# BatteryProtection.net
KiCad netlist of a schematic drawn in EAGLE
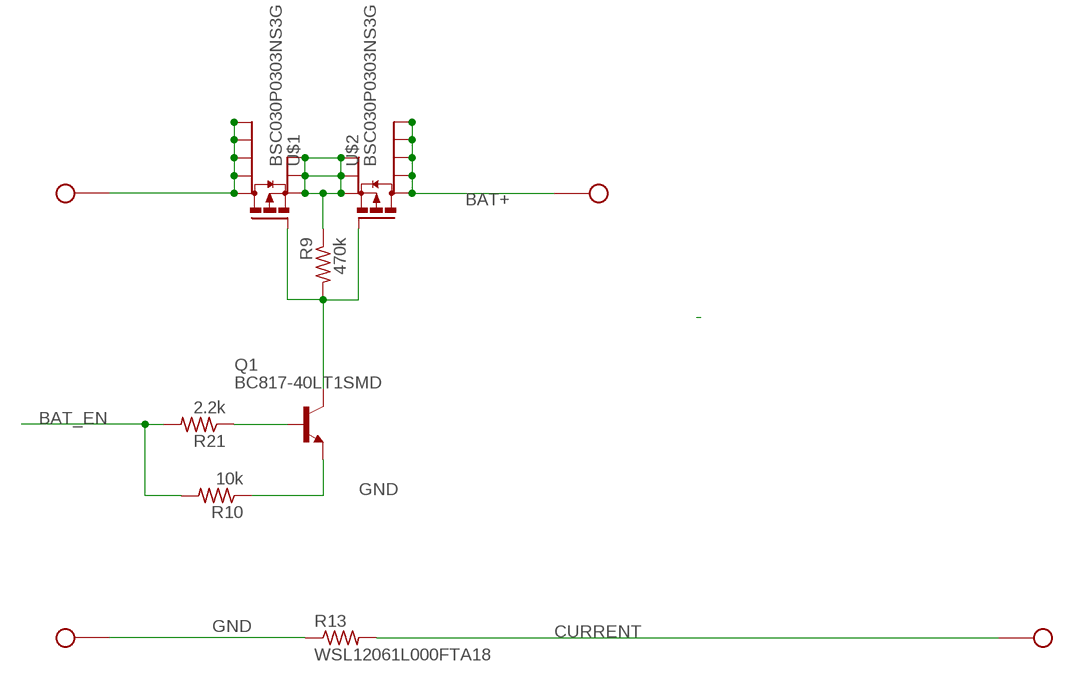
[diagram p0: schematic, sheet 1]
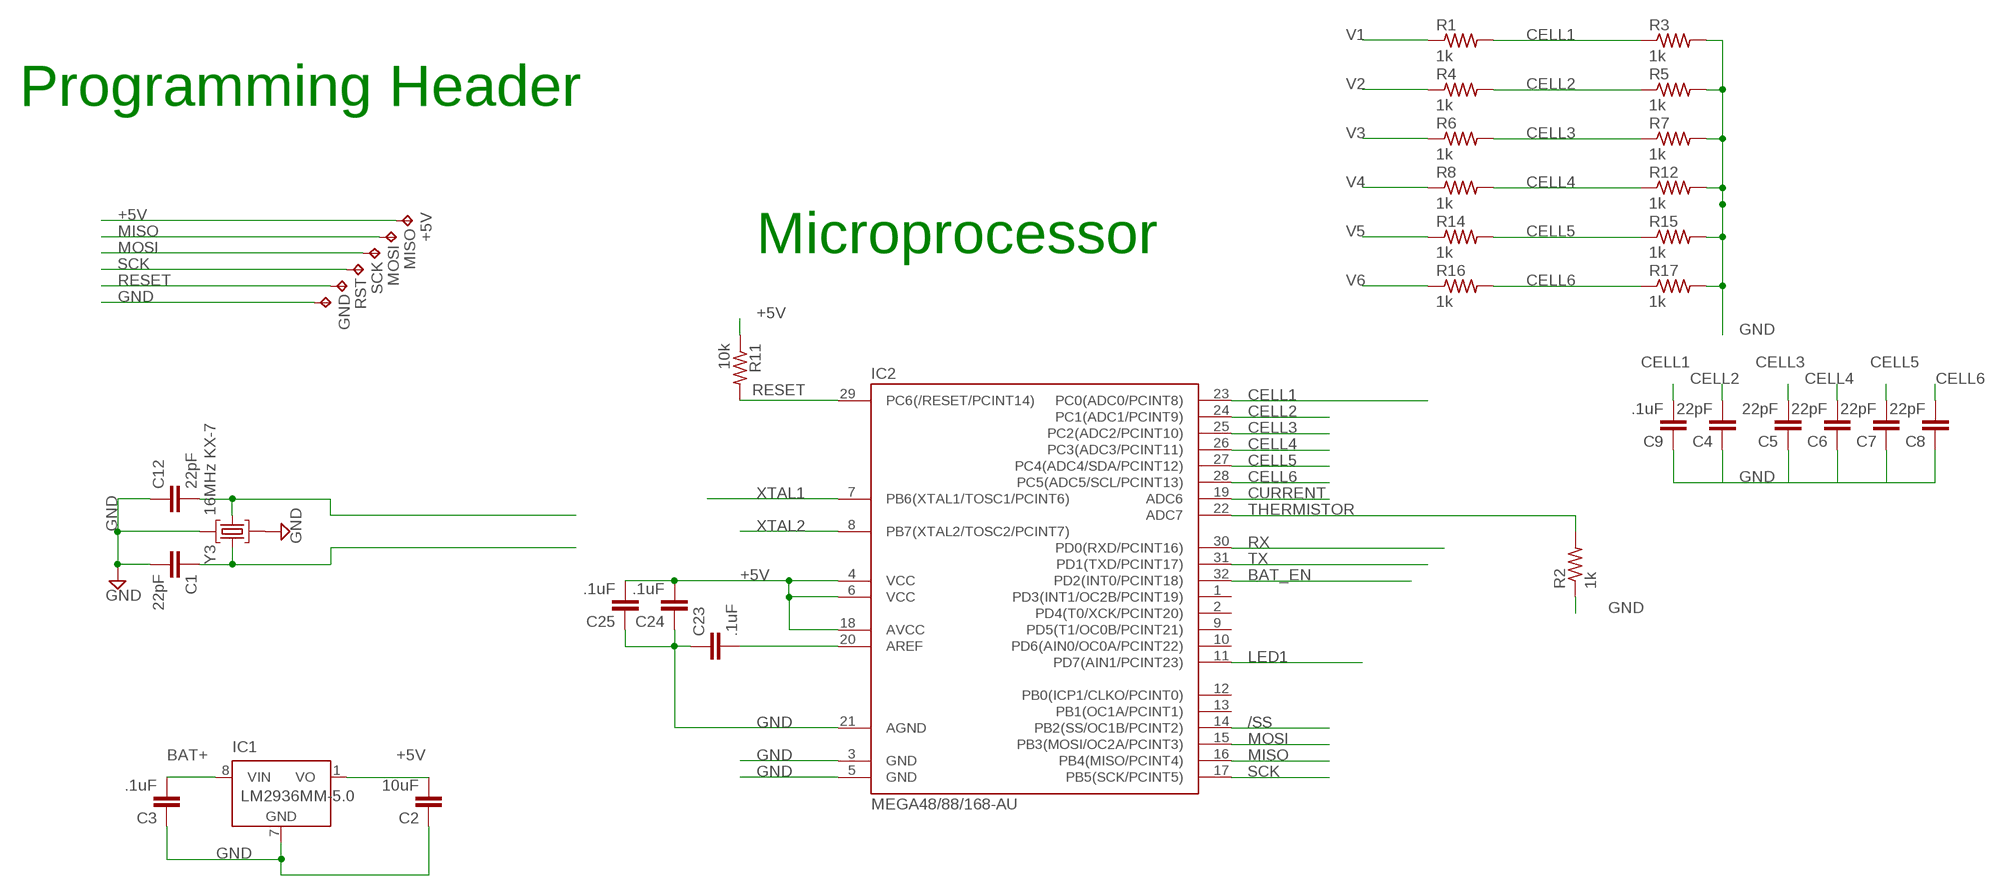
[diagram p1: schematic, sheet 2]

(export (version "E")
  (design (tool "Eeschema 10.0.6"))
  (components
    (comp (ref "+5V")
      (value "TPTP08R")
      (footprint "eagle-import:TP08R")
      (libsource (lib "eagle-import") (part "TPTP08R"))
    )
    (comp (ref "C1")
      (value "22pF")
      (footprint "eagle-import:C0402")
      (libsource (lib "eagle-import") (part "rcl_C-EUC0402"))
    )
    (comp (ref "C2")
      (value "10uF")
      (footprint "eagle-import:C0805")
      (libsource (lib "eagle-import") (part "rcl_C-EUC0805"))
    )
    (comp (ref "C3")
      (value ".1uF")
      (footprint "eagle-import:C0402")
      (libsource (lib "eagle-import") (part "rcl_C-EUC0402"))
    )
    (comp (ref "C4")
      (value "22pF")
      (footprint "eagle-import:C0402")
      (libsource (lib "eagle-import") (part "C-EUC0402"))
    )
    (comp (ref "C5")
      (value "22pF")
      (footprint "eagle-import:C0402")
      (libsource (lib "eagle-import") (part "C-EUC0402"))
    )
    (comp (ref "C6")
      (value "22pF")
      (footprint "eagle-import:C0402")
      (libsource (lib "eagle-import") (part "C-EUC0402"))
    )
    (comp (ref "C7")
      (value "22pF")
      (footprint "eagle-import:C0402")
      (libsource (lib "eagle-import") (part "C-EUC0402"))
    )
    (comp (ref "C8")
      (value "22pF")
      (footprint "eagle-import:C0402")
      (libsource (lib "eagle-import") (part "C-EUC0402"))
    )
    (comp (ref "C9")
      (value ".1uF")
      (footprint "eagle-import:C0402")
      (libsource (lib "eagle-import") (part "rcl_C-EUC0402"))
    )
    (comp (ref "C12")
      (value "22pF")
      (footprint "eagle-import:C0402")
      (libsource (lib "eagle-import") (part "C-EUC0402"))
    )
    (comp (ref "C23")
      (value ".1uF")
      (footprint "eagle-import:C0402")
      (libsource (lib "eagle-import") (part "rcl_C-EUC0402"))
    )
    (comp (ref "C24")
      (value ".1uF")
      (footprint "eagle-import:C0402")
      (libsource (lib "eagle-import") (part "rcl_C-EUC0402"))
    )
    (comp (ref "C25")
      (value ".1uF")
      (footprint "eagle-import:C0402")
      (libsource (lib "eagle-import") (part "rcl_C-EUC0402"))
    )
    (comp (ref "GND")
      (value "TPTP08R")
      (footprint "eagle-import:TP08R")
      (libsource (lib "eagle-import") (part "TPTP08R"))
    )
    (comp (ref "IC1")
      (value "LM2936MM-5.0")
      (footprint "eagle-import:MINI-SO8")
      (fields (field (name "MF") "NATIONAL SEMICONDUCTOR") (field (name "MPN") "LM2936MM-5.0/NOPB"))
      (libsource (lib "eagle-import") (part "LM2936?MM-5.0"))
    )
    (comp (ref "IC2")
      (value "MEGA48/88/168-AU")
      (footprint "eagle-import:TQFP32-08")
      (libsource (lib "eagle-import") (part "MEGA48/88/168-AU"))
    )
    (comp (ref "MISO")
      (value "TPTP08R")
      (footprint "eagle-import:TP08R")
      (libsource (lib "eagle-import") (part "TPTP08R"))
    )
    (comp (ref "MOSI")
      (value "TPTP08R")
      (footprint "eagle-import:TP08R")
      (libsource (lib "eagle-import") (part "TPTP08R"))
    )
    (comp (ref "R1")
      (value "1k")
      (footprint "eagle-import:R0402")
      (libsource (lib "eagle-import") (part "rcl_R-US_R0402"))
    )
    (comp (ref "R2")
      (value "1k")
      (footprint "eagle-import:R0402")
      (libsource (lib "eagle-import") (part "rcl_R-US_R0402"))
    )
    (comp (ref "R3")
      (value "1k")
      (footprint "eagle-import:R0402")
      (libsource (lib "eagle-import") (part "rcl_R-US_R0402"))
    )
    (comp (ref "R4")
      (value "1k")
      (footprint "eagle-import:R0402")
      (libsource (lib "eagle-import") (part "rcl_R-US_R0402"))
    )
    (comp (ref "R5")
      (value "1k")
      (footprint "eagle-import:R0402")
      (libsource (lib "eagle-import") (part "rcl_R-US_R0402"))
    )
    (comp (ref "R6")
      (value "1k")
      (footprint "eagle-import:R0402")
      (libsource (lib "eagle-import") (part "rcl_R-US_R0402"))
    )
    (comp (ref "R7")
      (value "1k")
      (footprint "eagle-import:R0402")
      (libsource (lib "eagle-import") (part "rcl_R-US_R0402"))
    )
    (comp (ref "R8")
      (value "1k")
      (footprint "eagle-import:R0402")
      (libsource (lib "eagle-import") (part "rcl_R-US_R0402"))
    )
    (comp (ref "R11")
      (value "10k")
      (footprint "eagle-import:R0402")
      (libsource (lib "eagle-import") (part "rcl_R-US_R0402"))
    )
    (comp (ref "R12")
      (value "1k")
      (footprint "eagle-import:R0402")
      (libsource (lib "eagle-import") (part "rcl_R-US_R0402"))
    )
    (comp (ref "R14")
      (value "1k")
      (footprint "eagle-import:R0402")
      (libsource (lib "eagle-import") (part "rcl_R-US_R0402"))
    )
    (comp (ref "R15")
      (value "1k")
      (footprint "eagle-import:R0402")
      (libsource (lib "eagle-import") (part "rcl_R-US_R0402"))
    )
    (comp (ref "R16")
      (value "1k")
      (footprint "eagle-import:R0402")
      (libsource (lib "eagle-import") (part "rcl_R-US_R0402"))
    )
    (comp (ref "R17")
      (value "1k")
      (footprint "eagle-import:R0402")
      (libsource (lib "eagle-import") (part "rcl_R-US_R0402"))
    )
    (comp (ref "RST")
      (value "TPTP08R")
      (footprint "eagle-import:TP08R")
      (libsource (lib "eagle-import") (part "TPTP08R"))
    )
    (comp (ref "SCK")
      (value "TPTP08R")
      (footprint "eagle-import:TP08R")
      (libsource (lib "eagle-import") (part "TPTP08R"))
    )
    (comp (ref "Y3")
      (value "16MHz KX-7")
      (footprint "eagle-import:CRYSTAL-3.2-2.5")
      (libsource (lib "eagle-import") (part "CRYSTAL-3.2-2.5"))
    )
    (comp (ref "Q1")
      (value "BC817-40LT1SMD")
      (footprint "eagle-import:SOT23-BEC")
      (libsource (lib "eagle-import") (part "BC817SMD-40LT1"))
    )
    (comp (ref "R9")
      (value "470k")
      (footprint "eagle-import:R0402")
      (libsource (lib "eagle-import") (part "R-US_R0402"))
    )
    (comp (ref "R10")
      (value "10k")
      (footprint "eagle-import:R0402")
      (libsource (lib "eagle-import") (part "R-US_R0402"))
    )
    (comp (ref "R13")
      (value "WSL12061L000FTA18")
      (footprint "eagle-import:R2512")
      (libsource (lib "eagle-import") (part "R-US_R2512"))
    )
    (comp (ref "R21")
      (value "2.2k")
      (footprint "eagle-import:R0402")
      (libsource (lib "eagle-import") (part "R-US_R0402"))
    )
    (comp (ref "U$1")
      (value "BSC030P0303NS3G")
      (footprint "eagle-import:PG-TDSON-8")
      (libsource (lib "eagle-import") (part "BSC030P0303NS3G"))
    )
    (comp (ref "U$2")
      (value "BSC030P0303NS3G")
      (footprint "eagle-import:PG-TDSON-8")
      (libsource (lib "eagle-import") (part "BSC030P0303NS3G"))
    )
    (comp (ref "X1")
      (value "SOLDER_HOLE18AWG")
      (footprint "eagle-import:SOLDER_HOLE_18")
      (libsource (lib "eagle-import") (part "SOLDER_HOLE18AWG"))
    )
    (comp (ref "X2")
      (value "SOLDER_HOLE18AWG")
      (footprint "eagle-import:SOLDER_HOLE_18")
      (libsource (lib "eagle-import") (part "SOLDER_HOLE18AWG"))
    )
    (comp (ref "X5")
      (value "SOLDER_HOLE18AWG")
      (footprint "eagle-import:SOLDER_HOLE_18")
      (libsource (lib "eagle-import") (part "SOLDER_HOLE18AWG"))
    )
    (comp (ref "X13")
      (value "SOLDER_HOLE18AWG")
      (footprint "eagle-import:SOLDER_HOLE_18")
      (libsource (lib "eagle-import") (part "SOLDER_HOLE18AWG"))
    )
  )
  (nets
    (net (code "1") (name "+5V") (class "Default")
      (node (ref "+5V") (pin "TP") (pinfunction "TP_TP") (pintype "input"))
      (node (ref "C2") (pin "2") (pinfunction "2_2") (pintype "passive"))
      (node (ref "C24") (pin "2") (pinfunction "2_2") (pintype "passive"))
      (node (ref "C25") (pin "2") (pinfunction "2_2") (pintype "passive"))
      (node (ref "IC1") (pin "1") (pinfunction "VO_1") (pintype "passive"))
      (node (ref "IC2") (pin "18") (pinfunction "AVCC_18") (pintype "passive"))
      (node (ref "IC2") (pin "4") (pinfunction "VCC_4") (pintype "power_in"))
      (node (ref "IC2") (pin "6") (pinfunction "VCC_6") (pintype "power_in"))
      (node (ref "R11") (pin "1") (pinfunction "1_1") (pintype "passive"))
    )
    (net (code "2") (name "BAT+") (class "Default")
      (node (ref "C3") (pin "2") (pinfunction "2_2") (pintype "passive"))
      (node (ref "IC1") (pin "8") (pinfunction "VIN_8") (pintype "input"))
      (node (ref "U$2") (pin "5") (pinfunction "D_5") (pintype "passive"))
      (node (ref "U$2") (pin "6") (pinfunction "D1_6") (pintype "passive"))
      (node (ref "U$2") (pin "7") (pinfunction "D2_7") (pintype "passive"))
      (node (ref "U$2") (pin "8") (pinfunction "D3_8") (pintype "passive"))
      (node (ref "U$2") (pin "TH") (pinfunction "D4_TH") (pintype "passive"))
      (node (ref "X1") (pin "1") (pinfunction "P$1_1") (pintype "bidirectional"))
    )
    (net (code "3") (name "BAT_EN") (class "Default")
      (node (ref "IC2") (pin "32") (pinfunction "PD2(INT0/PCINT18)_32") (pintype "bidirectional"))
      (node (ref "R10") (pin "2") (pinfunction "2_2") (pintype "passive"))
      (node (ref "R21") (pin "2") (pinfunction "2_2") (pintype "passive"))
    )
    (net (code "4") (name "CELL1") (class "Default")
      (node (ref "C9") (pin "2") (pinfunction "2_2") (pintype "passive"))
      (node (ref "IC2") (pin "23") (pinfunction "PC0(ADC0/PCINT8)_23") (pintype "bidirectional"))
      (node (ref "R1") (pin "2") (pinfunction "2_2") (pintype "passive"))
      (node (ref "R3") (pin "1") (pinfunction "1_1") (pintype "passive"))
    )
    (net (code "5") (name "CELL2") (class "Default")
      (node (ref "C4") (pin "2") (pinfunction "2_2") (pintype "passive"))
      (node (ref "IC2") (pin "24") (pinfunction "PC1(ADC1/PCINT9)_24") (pintype "bidirectional"))
      (node (ref "R4") (pin "2") (pinfunction "2_2") (pintype "passive"))
      (node (ref "R5") (pin "1") (pinfunction "1_1") (pintype "passive"))
    )
    (net (code "6") (name "CELL3") (class "Default")
      (node (ref "C5") (pin "2") (pinfunction "2_2") (pintype "passive"))
      (node (ref "IC2") (pin "25") (pinfunction "PC2(ADC2/PCINT10)_25") (pintype "bidirectional"))
      (node (ref "R6") (pin "2") (pinfunction "2_2") (pintype "passive"))
      (node (ref "R7") (pin "1") (pinfunction "1_1") (pintype "passive"))
    )
    (net (code "7") (name "CELL4") (class "Default")
      (node (ref "C6") (pin "2") (pinfunction "2_2") (pintype "passive"))
      (node (ref "IC2") (pin "26") (pinfunction "PC3(ADC3/PCINT11)_26") (pintype "bidirectional"))
      (node (ref "R12") (pin "1") (pinfunction "1_1") (pintype "passive"))
      (node (ref "R8") (pin "2") (pinfunction "2_2") (pintype "passive"))
    )
    (net (code "8") (name "CELL5") (class "Default")
      (node (ref "C7") (pin "2") (pinfunction "2_2") (pintype "passive"))
      (node (ref "IC2") (pin "27") (pinfunction "PC4(ADC4/SDA/PCINT12)_27") (pintype "bidirectional"))
      (node (ref "R14") (pin "2") (pinfunction "2_2") (pintype "passive"))
      (node (ref "R15") (pin "1") (pinfunction "1_1") (pintype "passive"))
    )
    (net (code "9") (name "CELL6") (class "Default")
      (node (ref "C8") (pin "2") (pinfunction "2_2") (pintype "passive"))
      (node (ref "IC2") (pin "28") (pinfunction "PC5(ADC5/SCL/PCINT13)_28") (pintype "bidirectional"))
      (node (ref "R16") (pin "2") (pinfunction "2_2") (pintype "passive"))
      (node (ref "R17") (pin "1") (pinfunction "1_1") (pintype "passive"))
    )
    (net (code "10") (name "CURRENT") (class "Default")
      (node (ref "IC2") (pin "19") (pinfunction "ADC6_19") (pintype "passive"))
      (node (ref "R13") (pin "2") (pinfunction "2_2") (pintype "passive"))
      (node (ref "X2") (pin "1") (pinfunction "P$1_1") (pintype "bidirectional"))
    )
    (net (code "11") (name "GND") (class "Default")
      (node (ref "C1") (pin "2") (pinfunction "2_2") (pintype "passive"))
      (node (ref "C12") (pin "1") (pinfunction "1_1") (pintype "passive"))
      (node (ref "C2") (pin "1") (pinfunction "1_1") (pintype "passive"))
      (node (ref "C23") (pin "1") (pinfunction "1_1") (pintype "passive"))
      (node (ref "C24") (pin "1") (pinfunction "1_1") (pintype "passive"))
      (node (ref "C25") (pin "1") (pinfunction "1_1") (pintype "passive"))
      (node (ref "C3") (pin "1") (pinfunction "1_1") (pintype "passive"))
      (node (ref "C4") (pin "1") (pinfunction "1_1") (pintype "passive"))
      (node (ref "C5") (pin "1") (pinfunction "1_1") (pintype "passive"))
      (node (ref "C6") (pin "1") (pinfunction "1_1") (pintype "passive"))
      (node (ref "C7") (pin "1") (pinfunction "1_1") (pintype "passive"))
      (node (ref "C8") (pin "1") (pinfunction "1_1") (pintype "passive"))
      (node (ref "C9") (pin "1") (pinfunction "1_1") (pintype "passive"))
      (node (ref "GND") (pin "TP") (pinfunction "TP_TP") (pintype "input"))
      (node (ref "IC1") (pin "7") (pinfunction "GND_7") (pintype "passive"))
      (node (ref "IC2") (pin "21") (pinfunction "AGND_21") (pintype "power_in"))
      (node (ref "IC2") (pin "3") (pinfunction "GND_3") (pintype "power_in"))
      (node (ref "IC2") (pin "5") (pinfunction "GND_5") (pintype "power_in"))
      (node (ref "Q1") (pin "E") (pinfunction "E_E") (pintype "passive"))
      (node (ref "R10") (pin "1") (pinfunction "1_1") (pintype "passive"))
      (node (ref "R12") (pin "2") (pinfunction "2_2") (pintype "passive"))
      (node (ref "R13") (pin "1") (pinfunction "1_1") (pintype "passive"))
      (node (ref "R15") (pin "2") (pinfunction "2_2") (pintype "passive"))
      (node (ref "R17") (pin "2") (pinfunction "2_2") (pintype "passive"))
      (node (ref "R2") (pin "1") (pinfunction "1_1") (pintype "passive"))
      (node (ref "R3") (pin "2") (pinfunction "2_2") (pintype "passive"))
      (node (ref "R5") (pin "2") (pinfunction "2_2") (pintype "passive"))
      (node (ref "R7") (pin "2") (pinfunction "2_2") (pintype "passive"))
      (node (ref "X13") (pin "1") (pinfunction "P$1_1") (pintype "bidirectional"))
      (node (ref "Y3") (pin "2") (pinfunction "GND_2") (pintype "passive"))
      (node (ref "Y3") (pin "4") (pinfunction "GND_4") (pintype "passive"))
    )
    (net (code "12") (name "LED1") (class "Default")
      (node (ref "IC2") (pin "11") (pinfunction "PD7(AIN1/PCINT23)_11") (pintype "bidirectional"))
    )
    (net (code "13") (name "MISO") (class "Default")
      (node (ref "IC2") (pin "16") (pinfunction "PB4(MISO/PCINT4)_16") (pintype "bidirectional"))
      (node (ref "MISO") (pin "TP") (pinfunction "TP_TP") (pintype "input"))
    )
    (net (code "14") (name "MOSI") (class "Default")
      (node (ref "IC2") (pin "15") (pinfunction "PB3(MOSI/OC2A/PCINT3)_15") (pintype "bidirectional"))
      (node (ref "MOSI") (pin "TP") (pinfunction "TP_TP") (pintype "input"))
    )
    (net (code "15") (name "Net-(IC2-AREF)") (class "Default")
      (node (ref "C23") (pin "2") (pinfunction "2_2") (pintype "passive"))
      (node (ref "IC2") (pin "20") (pinfunction "AREF_20") (pintype "passive"))
    )
    (net (code "16") (name "Net-(Q1-PadB)") (class "Default")
      (node (ref "Q1") (pin "B") (pinfunction "B_B") (pintype "passive"))
      (node (ref "R21") (pin "1") (pinfunction "1_1") (pintype "passive"))
    )
    (net (code "17") (name "Net-(U$1-D)") (class "Default")
      (node (ref "U$1") (pin "5") (pinfunction "D_5") (pintype "passive"))
      (node (ref "U$1") (pin "6") (pinfunction "D1_6") (pintype "passive"))
      (node (ref "U$1") (pin "7") (pinfunction "D2_7") (pintype "passive"))
      (node (ref "U$1") (pin "8") (pinfunction "D3_8") (pintype "passive"))
      (node (ref "U$1") (pin "TH") (pinfunction "D4_TH") (pintype "passive"))
      (node (ref "X5") (pin "1") (pinfunction "P$1_1") (pintype "bidirectional"))
    )
    (net (code "18") (name "Net-(U$1-G)") (class "Default")
      (node (ref "Q1") (pin "C") (pinfunction "C_C") (pintype "passive"))
      (node (ref "R9") (pin "2") (pinfunction "2_2") (pintype "passive"))
      (node (ref "U$1") (pin "4") (pinfunction "G_4") (pintype "passive"))
      (node (ref "U$2") (pin "4") (pinfunction "G_4") (pintype "passive"))
    )
    (net (code "19") (name "Net-(U$1-S)") (class "Default")
      (node (ref "R9") (pin "1") (pinfunction "1_1") (pintype "passive"))
      (node (ref "U$1") (pin "1") (pinfunction "S_1") (pintype "passive"))
      (node (ref "U$1") (pin "2") (pinfunction "S1_2") (pintype "passive"))
      (node (ref "U$1") (pin "3") (pinfunction "S2_3") (pintype "passive"))
      (node (ref "U$2") (pin "1") (pinfunction "S_1") (pintype "passive"))
      (node (ref "U$2") (pin "2") (pinfunction "S1_2") (pintype "passive"))
      (node (ref "U$2") (pin "3") (pinfunction "S2_3") (pintype "passive"))
    )
    (net (code "20") (name "RESET") (class "Default")
      (node (ref "IC2") (pin "29") (pinfunction "PC6(/RESET/PCINT14)_29") (pintype "bidirectional"))
      (node (ref "R11") (pin "2") (pinfunction "2_2") (pintype "passive"))
      (node (ref "RST") (pin "TP") (pinfunction "TP_TP") (pintype "input"))
    )
    (net (code "21") (name "RX") (class "Default")
      (node (ref "IC2") (pin "30") (pinfunction "PD0(RXD/PCINT16)_30") (pintype "bidirectional"))
    )
    (net (code "22") (name "SCK") (class "Default")
      (node (ref "IC2") (pin "17") (pinfunction "PB5(SCK/PCINT5)_17") (pintype "bidirectional"))
      (node (ref "SCK") (pin "TP") (pinfunction "TP_TP") (pintype "input"))
    )
    (net (code "23") (name "THERMISTOR") (class "Default")
      (node (ref "IC2") (pin "22") (pinfunction "ADC7_22") (pintype "passive"))
      (node (ref "R2") (pin "2") (pinfunction "2_2") (pintype "passive"))
    )
    (net (code "24") (name "TX") (class "Default")
      (node (ref "IC2") (pin "31") (pinfunction "PD1(TXD/PCINT17)_31") (pintype "bidirectional"))
    )
    (net (code "25") (name "V1") (class "Default")
      (node (ref "R1") (pin "1") (pinfunction "1_1") (pintype "passive"))
    )
    (net (code "26") (name "V2") (class "Default")
      (node (ref "R4") (pin "1") (pinfunction "1_1") (pintype "passive"))
    )
    (net (code "27") (name "V3") (class "Default")
      (node (ref "R6") (pin "1") (pinfunction "1_1") (pintype "passive"))
    )
    (net (code "28") (name "V4") (class "Default")
      (node (ref "R8") (pin "1") (pinfunction "1_1") (pintype "passive"))
    )
    (net (code "29") (name "V5") (class "Default")
      (node (ref "R14") (pin "1") (pinfunction "1_1") (pintype "passive"))
    )
    (net (code "30") (name "V6") (class "Default")
      (node (ref "R16") (pin "1") (pinfunction "1_1") (pintype "passive"))
    )
    (net (code "31") (name "XTAL1") (class "Default")
      (node (ref "C1") (pin "1") (pinfunction "1_1") (pintype "passive"))
      (node (ref "IC2") (pin "7") (pinfunction "PB6(XTAL1/TOSC1/PCINT6)_7") (pintype "bidirectional"))
      (node (ref "Y3") (pin "3") (pinfunction "C2_3") (pintype "passive"))
    )
    (net (code "32") (name "XTAL2") (class "Default")
      (node (ref "C12") (pin "2") (pinfunction "2_2") (pintype "passive"))
      (node (ref "IC2") (pin "8") (pinfunction "PB7(XTAL2/TOSC2/PCINT7)_8") (pintype "bidirectional"))
      (node (ref "Y3") (pin "1") (pinfunction "C1_1") (pintype "passive"))
    )
    (net (code "33") (name "unconnected-(IC2-PB0(ICP1{slash}CLKO{slash}PCINT0)-Pad12)") (class "Default")
      (node (ref "IC2") (pin "12") (pinfunction "PB0(ICP1/CLKO/PCINT0)_12") (pintype "bidirectional"))
    )
    (net (code "34") (name "unconnected-(IC2-PB1(OC1A{slash}PCINT1)-Pad13)") (class "Default")
      (node (ref "IC2") (pin "13") (pinfunction "PB1(OC1A/PCINT1)_13") (pintype "bidirectional"))
    )
    (net (code "35") (name "unconnected-(IC2-PD3(INT1{slash}OC2B{slash}PCINT19)-Pad1)") (class "Default")
      (node (ref "IC2") (pin "1") (pinfunction "PD3(INT1/OC2B/PCINT19)_1") (pintype "bidirectional"))
    )
    (net (code "36") (name "unconnected-(IC2-PD4(T0{slash}XCK{slash}PCINT20)-Pad2)") (class "Default")
      (node (ref "IC2") (pin "2") (pinfunction "PD4(T0/XCK/PCINT20)_2") (pintype "bidirectional"))
    )
    (net (code "37") (name "unconnected-(IC2-PD5(T1{slash}OC0B{slash}PCINT21)-Pad9)") (class "Default")
      (node (ref "IC2") (pin "9") (pinfunction "PD5(T1/OC0B/PCINT21)_9") (pintype "bidirectional"))
    )
    (net (code "38") (name "unconnected-(IC2-PD6(AIN0{slash}OC0A{slash}PCINT22)-Pad10)") (class "Default")
      (node (ref "IC2") (pin "10") (pinfunction "PD6(AIN0/OC0A/PCINT22)_10") (pintype "bidirectional"))
    )
    (net (code "39") (name "{slash}SS") (class "Default")
      (node (ref "IC2") (pin "14") (pinfunction "PB2(SS/OC1B/PCINT2)_14") (pintype "bidirectional"))
    )
  )
)
